# the_mill.net
KiCad netlist of a schematic drawn in EAGLE
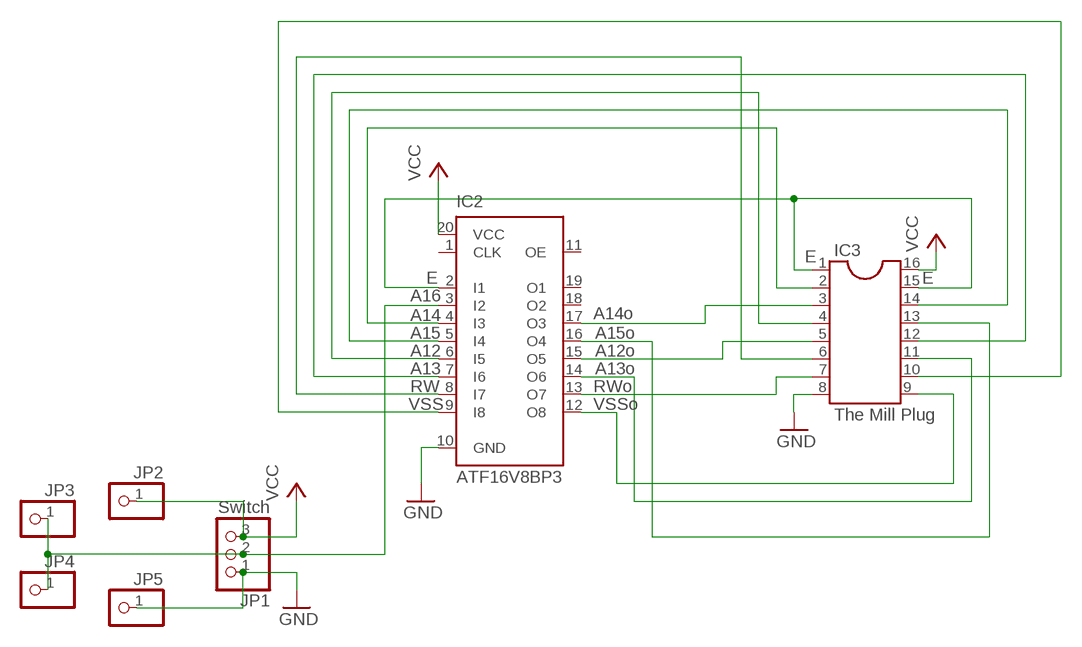
[diagram p0: schematic, sheet 1]

(export (version "E")
  (design (tool "Eeschema 10.0.6"))
  (components
    (comp (ref "IC2")
      (value "ATF16V8BP3")
      (footprint "eagle-import:DIL20")
      (fields (field (name "MPN") "ATF16V8CZ-15PU"))
      (libsource (lib "eagle-import") (part "ATF16V8BP3"))
    )
    (comp (ref "IC3")
      (value "The Mill Plug")
      (footprint "eagle-import:DIL16")
      (libsource (lib "eagle-import") (part "DIL16"))
    )
    (comp (ref "JP1")
      (value "Switch")
      (footprint "eagle-import:1X03")
      (libsource (lib "eagle-import") (part "PINHD-1X3"))
    )
    (comp (ref "JP2")
      (value "PINHD-1X1")
      (footprint "eagle-import:1X01")
      (libsource (lib "eagle-import") (part "PINHD-1X1"))
    )
    (comp (ref "JP3")
      (value "PINHD-1X1")
      (footprint "eagle-import:1X01")
      (libsource (lib "eagle-import") (part "PINHD-1X1"))
    )
    (comp (ref "JP4")
      (value "PINHD-1X1")
      (footprint "eagle-import:1X01")
      (libsource (lib "eagle-import") (part "PINHD-1X1"))
    )
    (comp (ref "JP5")
      (value "PINHD-1X1")
      (footprint "eagle-import:1X01")
      (libsource (lib "eagle-import") (part "PINHD-1X1"))
    )
  )
  (nets
    (net (code "1") (name "GND") (class "Default")
      (node (ref "IC2") (pin "10") (pinfunction "GND_10") (pintype "power_in"))
      (node (ref "IC3") (pin "8") (pinfunction "8_8") (pintype "passive"))
      (node (ref "JP1") (pin "1") (pinfunction "1_1") (pintype "passive"))
      (node (ref "JP5") (pin "1") (pinfunction "1_1") (pintype "passive"))
    )
    (net (code "2") (name "Net-(IC2-I1)") (class "Default")
      (node (ref "IC2") (pin "2") (pinfunction "I1_2") (pintype "input"))
      (node (ref "IC3") (pin "1") (pinfunction "1_1") (pintype "passive"))
      (node (ref "IC3") (pin "15") (pinfunction "15_15") (pintype "passive"))
    )
    (net (code "3") (name "Net-(IC2-I2)") (class "Default")
      (node (ref "IC2") (pin "3") (pinfunction "I2_3") (pintype "input"))
      (node (ref "JP1") (pin "2") (pinfunction "2_2") (pintype "passive"))
      (node (ref "JP3") (pin "1") (pinfunction "1_1") (pintype "passive"))
      (node (ref "JP4") (pin "1") (pinfunction "1_1") (pintype "passive"))
    )
    (net (code "4") (name "Net-(IC2-I3)") (class "Default")
      (node (ref "IC2") (pin "4") (pinfunction "I3_4") (pintype "input"))
      (node (ref "IC3") (pin "2") (pinfunction "2_2") (pintype "passive"))
    )
    (net (code "5") (name "Net-(IC2-I4)") (class "Default")
      (node (ref "IC2") (pin "5") (pinfunction "I4_5") (pintype "input"))
      (node (ref "IC3") (pin "14") (pinfunction "14_14") (pintype "passive"))
    )
    (net (code "6") (name "Net-(IC2-I5)") (class "Default")
      (node (ref "IC2") (pin "6") (pinfunction "I5_6") (pintype "input"))
      (node (ref "IC3") (pin "4") (pinfunction "4_4") (pintype "passive"))
    )
    (net (code "7") (name "Net-(IC2-I6)") (class "Default")
      (node (ref "IC2") (pin "7") (pinfunction "I6_7") (pintype "input"))
      (node (ref "IC3") (pin "12") (pinfunction "12_12") (pintype "passive"))
    )
    (net (code "8") (name "Net-(IC2-I7)") (class "Default")
      (node (ref "IC2") (pin "8") (pinfunction "I7_8") (pintype "input"))
      (node (ref "IC3") (pin "6") (pinfunction "6_6") (pintype "passive"))
    )
    (net (code "9") (name "Net-(IC2-I8)") (class "Default")
      (node (ref "IC2") (pin "9") (pinfunction "I8_9") (pintype "input"))
      (node (ref "IC3") (pin "10") (pinfunction "10_10") (pintype "passive"))
    )
    (net (code "10") (name "Net-(IC2-O3)") (class "Default")
      (node (ref "IC2") (pin "17") (pinfunction "O3_17") (pintype "output"))
      (node (ref "IC3") (pin "3") (pinfunction "3_3") (pintype "passive"))
    )
    (net (code "11") (name "Net-(IC2-O4)") (class "Default")
      (node (ref "IC2") (pin "16") (pinfunction "O4_16") (pintype "output"))
      (node (ref "IC3") (pin "13") (pinfunction "13_13") (pintype "passive"))
    )
    (net (code "12") (name "Net-(IC2-O5)") (class "Default")
      (node (ref "IC2") (pin "15") (pinfunction "O5_15") (pintype "output"))
      (node (ref "IC3") (pin "5") (pinfunction "5_5") (pintype "passive"))
    )
    (net (code "13") (name "Net-(IC2-O6)") (class "Default")
      (node (ref "IC2") (pin "14") (pinfunction "O6_14") (pintype "output"))
      (node (ref "IC3") (pin "11") (pinfunction "11_11") (pintype "passive"))
    )
    (net (code "14") (name "Net-(IC2-O7)") (class "Default")
      (node (ref "IC2") (pin "13") (pinfunction "O7_13") (pintype "output"))
      (node (ref "IC3") (pin "7") (pinfunction "7_7") (pintype "passive"))
    )
    (net (code "15") (name "Net-(IC2-O8)") (class "Default")
      (node (ref "IC2") (pin "12") (pinfunction "O8_12") (pintype "output"))
      (node (ref "IC3") (pin "9") (pinfunction "9_9") (pintype "passive"))
    )
    (net (code "16") (name "VCC") (class "Default")
      (node (ref "IC2") (pin "20") (pinfunction "VCC_20") (pintype "power_in"))
      (node (ref "IC3") (pin "16") (pinfunction "16_16") (pintype "passive"))
      (node (ref "JP1") (pin "3") (pinfunction "3_3") (pintype "passive"))
      (node (ref "JP2") (pin "1") (pinfunction "1_1") (pintype "passive"))
    )
    (net (code "17") (name "unconnected-(IC2-CLK-Pad1)") (class "Default")
      (node (ref "IC2") (pin "1") (pinfunction "CLK_1") (pintype "input"))
    )
    (net (code "18") (name "unconnected-(IC2-O1-Pad19)") (class "Default")
      (node (ref "IC2") (pin "19") (pinfunction "O1_19") (pintype "output"))
    )
    (net (code "19") (name "unconnected-(IC2-O2-Pad18)") (class "Default")
      (node (ref "IC2") (pin "18") (pinfunction "O2_18") (pintype "output"))
    )
    (net (code "20") (name "unconnected-(IC2-OE-Pad11)") (class "Default")
      (node (ref "IC2") (pin "11") (pinfunction "OE_11") (pintype "input"))
    )
  )
)
